# schemat.net
KiCad netlist of a schematic drawn in EAGLE
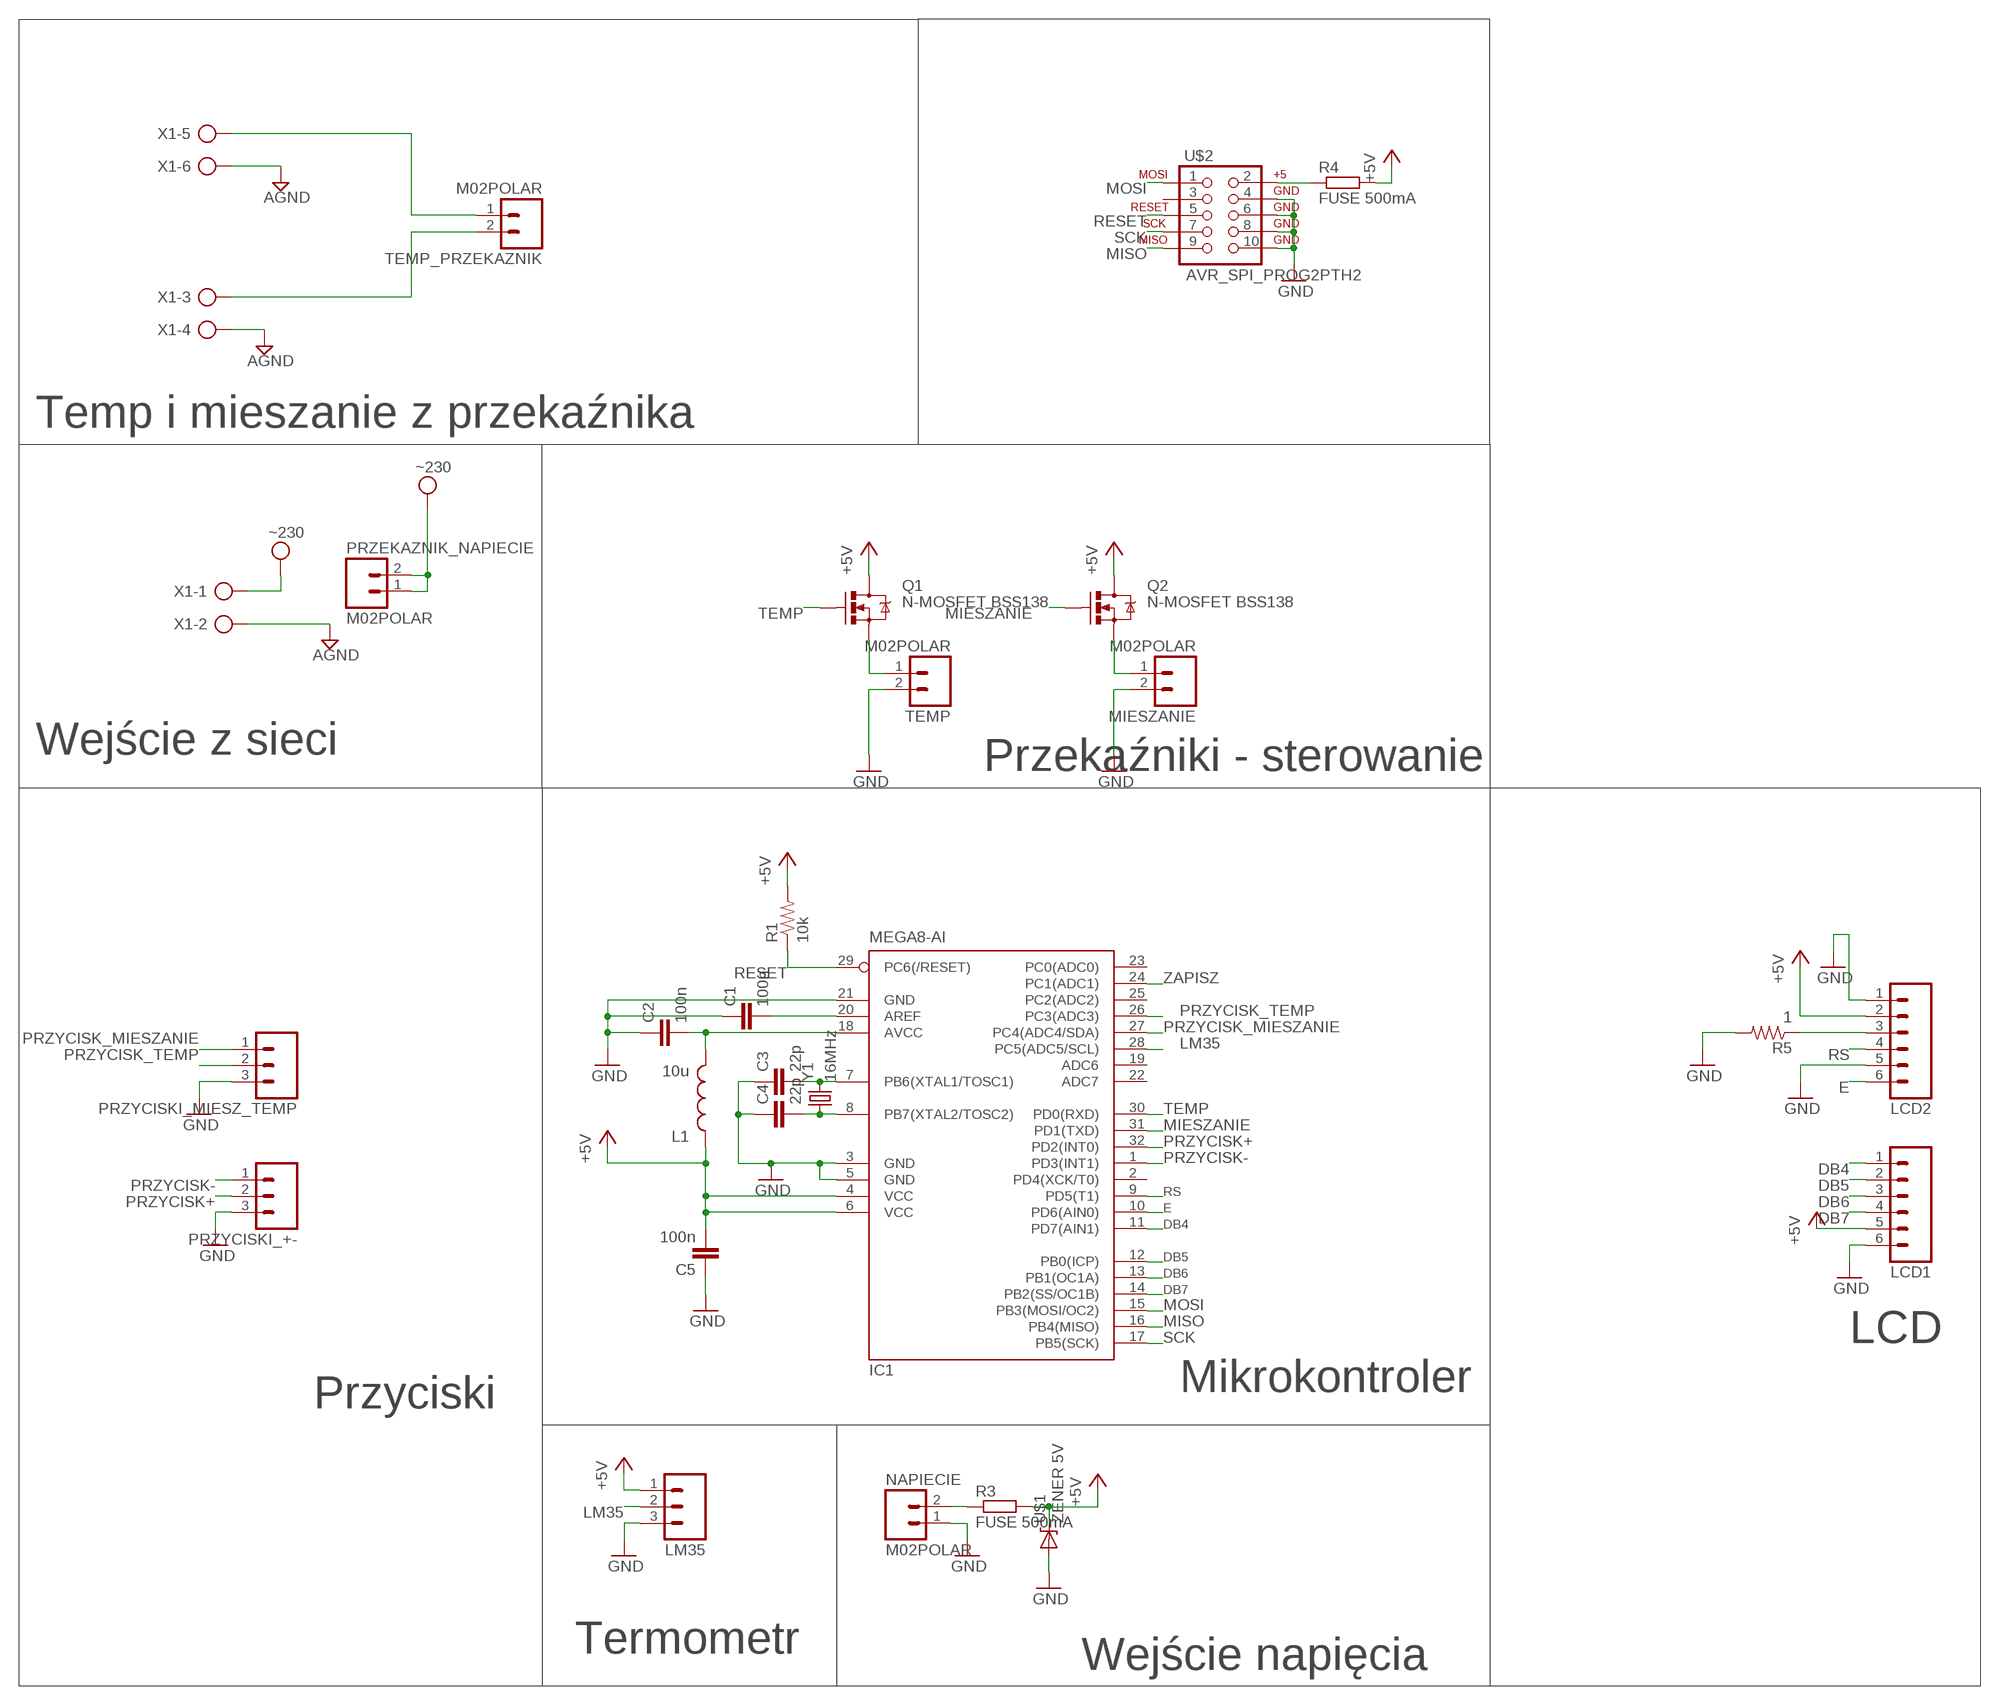
[diagram p0: schematic, sheet 1]

(export (version "E")
  (design (tool "Eeschema 10.0.6"))
  (components
    (comp (ref "C1")
      (value "100n")
      (footprint "eagle-import:0805")
      (libsource (lib "eagle-import") (part "CAP0805"))
    )
    (comp (ref "C2")
      (value "100n")
      (footprint "eagle-import:0805")
      (libsource (lib "eagle-import") (part "CAP0805"))
    )
    (comp (ref "C3")
      (value "22p")
      (footprint "eagle-import:0805")
      (libsource (lib "eagle-import") (part "CAP0805"))
    )
    (comp (ref "C4")
      (value "22p")
      (footprint "eagle-import:0805")
      (libsource (lib "eagle-import") (part "CAP0805"))
    )
    (comp (ref "C5")
      (value "100n")
      (footprint "eagle-import:0805")
      (libsource (lib "eagle-import") (part "CAP0805"))
    )
    (comp (ref "IC1")
      (value "MEGA8-AI")
      (footprint "eagle-import:TQFP32-08")
      (fields (field (name "MPN") "ATMEGA8-16AU"))
      (libsource (lib "eagle-import") (part "MEGA8-AI"))
    )
    (comp (ref "L1")
      (value "10u")
      (footprint "eagle-import:0805")
      (libsource (lib "eagle-import") (part "INDUCTOR0805"))
    )
    (comp (ref "LCD1")
      (value "M06POLAR")
      (footprint "eagle-import:MOLEX-1X6")
      (libsource (lib "eagle-import") (part "M06POLAR"))
    )
    (comp (ref "LCD2")
      (value "M06POLAR")
      (footprint "eagle-import:MOLEX-1X6")
      (libsource (lib "eagle-import") (part "M06POLAR"))
    )
    (comp (ref "LM35")
      (value "M03POLAR")
      (footprint "eagle-import:MOLEX-1X3")
      (libsource (lib "eagle-import") (part "M03POLAR"))
    )
    (comp (ref "MIESZANIE")
      (value "M02POLAR")
      (footprint "eagle-import:MOLEX-1X2")
      (libsource (lib "eagle-import") (part "M02POLAR"))
    )
    (comp (ref "NAPIECIE")
      (value "M02POLAR")
      (footprint "eagle-import:MOLEX-1X2")
      (libsource (lib "eagle-import") (part "M02POLAR"))
    )
    (comp (ref "PRZEKAZNIK_NAPIECIE")
      (value "M02POLAR")
      (footprint "eagle-import:MOLEX-1X2")
      (libsource (lib "eagle-import") (part "M02POLAR"))
    )
    (comp (ref "PRZYCISKI_+-")
      (value "M03POLAR")
      (footprint "eagle-import:MOLEX-1X3")
      (libsource (lib "eagle-import") (part "M03POLAR"))
    )
    (comp (ref "PRZYCISKI_MIESZ_TEMP")
      (value "M03POLAR")
      (footprint "eagle-import:MOLEX-1X3")
      (libsource (lib "eagle-import") (part "M03POLAR"))
    )
    (comp (ref "Q1")
      (value "N-MOSFET BSS138")
      (footprint "eagle-import:SOT23")
      (libsource (lib "eagle-import") (part "MOSFET-NCHANNELBSS123LT1G"))
    )
    (comp (ref "Q2")
      (value "N-MOSFET BSS138")
      (footprint "eagle-import:SOT23")
      (libsource (lib "eagle-import") (part "MOSFET-NCHANNELBSS123LT1G"))
    )
    (comp (ref "R1")
      (value "10k")
      (footprint "eagle-import:0805")
      (libsource (lib "eagle-import") (part "RESISTOR0805-RES"))
    )
    (comp (ref "R3")
      (value "FUSE 500mA")
      (footprint "eagle-import:M0805")
      (libsource (lib "eagle-import") (part "R-EU_M0805"))
    )
    (comp (ref "R4")
      (value "FUSE 500mA")
      (footprint "eagle-import:M0805")
      (libsource (lib "eagle-import") (part "R-EU_M0805"))
    )
    (comp (ref "R5")
      (value "1")
      (footprint "eagle-import:0805")
      (libsource (lib "eagle-import") (part "RESISTOR0805-RES"))
    )
    (comp (ref "TEMP")
      (value "M02POLAR")
      (footprint "eagle-import:MOLEX-1X2")
      (libsource (lib "eagle-import") (part "M02POLAR"))
    )
    (comp (ref "TEMP_PRZEKAZNIK")
      (value "M02POLAR")
      (footprint "eagle-import:MOLEX-1X2")
      (libsource (lib "eagle-import") (part "M02POLAR"))
    )
    (comp (ref "U$1")
      (value "ZENER 5V")
      (footprint "eagle-import:SMB-DIODE")
      (libsource (lib "eagle-import") (part "DIODE-ZENERSMB"))
    )
    (comp (ref "U$2")
      (value "AVR_SPI_PROG2PTH2")
      (footprint "eagle-import:2X5-SHROUDED")
      (libsource (lib "eagle-import") (part "AVR_SPI_PROG2PTH2"))
    )
    (comp (ref "X1")
      (value "AK300/6")
      (footprint "eagle-import:AK300_6")
      (libsource (lib "eagle-import") (part "AK300/6"))
    )
    (comp (ref "Y1")
      (value "16MHz")
      (footprint "eagle-import:HC49US")
      (libsource (lib "eagle-import") (part "CRYSTALHC49US"))
    )
  )
  (nets
    (net (code "1") (name "+5V") (class "Default")
      (node (ref "C5") (pin "2") (pinfunction "2_2") (pintype "passive"))
      (node (ref "IC1") (pin "4") (pinfunction "VCC_4") (pintype "power_in"))
      (node (ref "IC1") (pin "6") (pinfunction "VCC_6") (pintype "power_in"))
      (node (ref "L1") (pin "1") (pinfunction "1_1") (pintype "passive"))
      (node (ref "LCD1") (pin "5") (pinfunction "5_5") (pintype "passive"))
      (node (ref "LCD2") (pin "2") (pinfunction "2_2") (pintype "passive"))
      (node (ref "LM35") (pin "1") (pinfunction "1_1") (pintype "passive"))
      (node (ref "Q1") (pin "3") (pinfunction "D_3") (pintype "passive"))
      (node (ref "Q2") (pin "3") (pinfunction "D_3") (pintype "passive"))
      (node (ref "R1") (pin "2") (pinfunction "2_2") (pintype "passive"))
      (node (ref "R3") (pin "2") (pinfunction "2_2") (pintype "passive"))
      (node (ref "R4") (pin "2") (pinfunction "2_2") (pintype "passive"))
      (node (ref "U$1") (pin "C") (pinfunction "C_C") (pintype "passive"))
    )
    (net (code "2") (name "/DB4") (class "Default")
      (node (ref "IC1") (pin "11") (pinfunction "PD7(AIN1)_11") (pintype "bidirectional"))
      (node (ref "LCD1") (pin "1") (pinfunction "1_1") (pintype "passive"))
    )
    (net (code "3") (name "/DB5") (class "Default")
      (node (ref "IC1") (pin "12") (pinfunction "PB0(ICP)_12") (pintype "bidirectional"))
      (node (ref "LCD1") (pin "2") (pinfunction "2_2") (pintype "passive"))
    )
    (net (code "4") (name "/DB6") (class "Default")
      (node (ref "IC1") (pin "13") (pinfunction "PB1(OC1A)_13") (pintype "bidirectional"))
      (node (ref "LCD1") (pin "3") (pinfunction "3_3") (pintype "passive"))
    )
    (net (code "5") (name "/DB7") (class "Default")
      (node (ref "IC1") (pin "14") (pinfunction "PB2(SS/OC1B)_14") (pintype "bidirectional"))
      (node (ref "LCD1") (pin "4") (pinfunction "4_4") (pintype "passive"))
    )
    (net (code "6") (name "/E") (class "Default")
      (node (ref "IC1") (pin "10") (pinfunction "PD6(AIN0)_10") (pintype "bidirectional"))
      (node (ref "LCD2") (pin "6") (pinfunction "6_6") (pintype "passive"))
    )
    (net (code "7") (name "/LM35") (class "Default")
      (node (ref "IC1") (pin "28") (pinfunction "PC5(ADC5/SCL)_28") (pintype "bidirectional"))
      (node (ref "LM35") (pin "2") (pinfunction "2_2") (pintype "passive"))
    )
    (net (code "8") (name "/MIESZANIE") (class "Default")
      (node (ref "IC1") (pin "31") (pinfunction "PD1(TXD)_31") (pintype "bidirectional"))
      (node (ref "Q2") (pin "1") (pinfunction "G_1") (pintype "passive"))
    )
    (net (code "9") (name "/MISO") (class "Default")
      (node (ref "IC1") (pin "16") (pinfunction "PB4(MISO)_16") (pintype "bidirectional"))
      (node (ref "U$2") (pin "9") (pinfunction "9_9") (pintype "passive"))
    )
    (net (code "10") (name "/MOSI") (class "Default")
      (node (ref "IC1") (pin "15") (pinfunction "PB3(MOSI/OC2)_15") (pintype "bidirectional"))
      (node (ref "U$2") (pin "1") (pinfunction "1_1") (pintype "passive"))
    )
    (net (code "11") (name "/PRZYCISK+") (class "Default")
      (node (ref "IC1") (pin "32") (pinfunction "PD2(INT0)_32") (pintype "bidirectional"))
      (node (ref "PRZYCISKI_+-") (pin "2") (pinfunction "2_2") (pintype "passive"))
    )
    (net (code "12") (name "/PRZYCISK-") (class "Default")
      (node (ref "IC1") (pin "1") (pinfunction "PD3(INT1)_1") (pintype "bidirectional"))
      (node (ref "PRZYCISKI_+-") (pin "1") (pinfunction "1_1") (pintype "passive"))
    )
    (net (code "13") (name "/PRZYCISK_MIESZANIE") (class "Default")
      (node (ref "IC1") (pin "27") (pinfunction "PC4(ADC4/SDA)_27") (pintype "bidirectional"))
      (node (ref "PRZYCISKI_MIESZ_TEMP") (pin "1") (pinfunction "1_1") (pintype "passive"))
    )
    (net (code "14") (name "/PRZYCISK_TEMP") (class "Default")
      (node (ref "IC1") (pin "26") (pinfunction "PC3(ADC3)_26") (pintype "bidirectional"))
      (node (ref "PRZYCISKI_MIESZ_TEMP") (pin "2") (pinfunction "2_2") (pintype "passive"))
    )
    (net (code "15") (name "/RESET") (class "Default")
      (node (ref "IC1") (pin "29") (pinfunction "PC6(/RESET)_29") (pintype "bidirectional"))
      (node (ref "R1") (pin "1") (pinfunction "1_1") (pintype "passive"))
      (node (ref "U$2") (pin "5") (pinfunction "5_5") (pintype "passive"))
    )
    (net (code "16") (name "/RS") (class "Default")
      (node (ref "IC1") (pin "9") (pinfunction "PD5(T1)_9") (pintype "bidirectional"))
      (node (ref "LCD2") (pin "4") (pinfunction "4_4") (pintype "passive"))
    )
    (net (code "17") (name "/SCK") (class "Default")
      (node (ref "IC1") (pin "17") (pinfunction "PB5(SCK)_17") (pintype "bidirectional"))
      (node (ref "U$2") (pin "7") (pinfunction "7_7") (pintype "passive"))
    )
    (net (code "18") (name "/TEMP") (class "Default")
      (node (ref "IC1") (pin "30") (pinfunction "PD0(RXD)_30") (pintype "bidirectional"))
      (node (ref "Q1") (pin "1") (pinfunction "G_1") (pintype "passive"))
    )
    (net (code "19") (name "/ZAPISZ") (class "Default")
      (node (ref "IC1") (pin "24") (pinfunction "PC1(ADC1)_24") (pintype "bidirectional"))
    )
    (net (code "20") (name "AGND") (class "Default")
      (node (ref "X1") (pin "2") (pinfunction "KL_2") (pintype "passive"))
      (node (ref "X1") (pin "4") (pinfunction "KL_4") (pintype "passive"))
      (node (ref "X1") (pin "6") (pinfunction "KL_6") (pintype "passive"))
    )
    (net (code "21") (name "GND") (class "Default")
      (node (ref "C1") (pin "1") (pinfunction "1_1") (pintype "passive"))
      (node (ref "C2") (pin "1") (pinfunction "1_1") (pintype "passive"))
      (node (ref "C3") (pin "1") (pinfunction "1_1") (pintype "passive"))
      (node (ref "C4") (pin "1") (pinfunction "1_1") (pintype "passive"))
      (node (ref "C5") (pin "1") (pinfunction "1_1") (pintype "passive"))
      (node (ref "IC1") (pin "21") (pinfunction "GND_21") (pintype "power_in"))
      (node (ref "IC1") (pin "3") (pinfunction "GND_3") (pintype "power_in"))
      (node (ref "IC1") (pin "5") (pinfunction "GND_5") (pintype "power_in"))
      (node (ref "LCD1") (pin "6") (pinfunction "6_6") (pintype "passive"))
      (node (ref "LCD2") (pin "1") (pinfunction "1_1") (pintype "passive"))
      (node (ref "LCD2") (pin "5") (pinfunction "5_5") (pintype "passive"))
      (node (ref "LM35") (pin "3") (pinfunction "3_3") (pintype "passive"))
      (node (ref "MIESZANIE") (pin "2") (pinfunction "2_2") (pintype "passive"))
      (node (ref "NAPIECIE") (pin "1") (pinfunction "1_1") (pintype "passive"))
      (node (ref "PRZYCISKI_+-") (pin "3") (pinfunction "3_3") (pintype "passive"))
      (node (ref "PRZYCISKI_MIESZ_TEMP") (pin "3") (pinfunction "3_3") (pintype "passive"))
      (node (ref "R5") (pin "2") (pinfunction "2_2") (pintype "passive"))
      (node (ref "TEMP") (pin "2") (pinfunction "2_2") (pintype "passive"))
      (node (ref "U$1") (pin "A") (pinfunction "A_A") (pintype "passive"))
      (node (ref "U$2") (pin "10") (pinfunction "10_10") (pintype "passive"))
      (node (ref "U$2") (pin "4") (pinfunction "4_4") (pintype "passive"))
      (node (ref "U$2") (pin "6") (pinfunction "6_6") (pintype "passive"))
      (node (ref "U$2") (pin "8") (pinfunction "8_8") (pintype "passive"))
    )
    (net (code "22") (name "Net-(IC1-AREF)") (class "Default")
      (node (ref "C1") (pin "2") (pinfunction "2_2") (pintype "passive"))
      (node (ref "IC1") (pin "20") (pinfunction "AREF_20") (pintype "passive"))
    )
    (net (code "23") (name "Net-(IC1-AVCC)") (class "Default")
      (node (ref "C2") (pin "2") (pinfunction "2_2") (pintype "passive"))
      (node (ref "IC1") (pin "18") (pinfunction "AVCC_18") (pintype "power_in"))
      (node (ref "L1") (pin "2") (pinfunction "2_2") (pintype "passive"))
    )
    (net (code "24") (name "Net-(IC1-PB6(XTAL1{slash}TOSC1))") (class "Default")
      (node (ref "C3") (pin "2") (pinfunction "2_2") (pintype "passive"))
      (node (ref "IC1") (pin "7") (pinfunction "PB6(XTAL1/TOSC1)_7") (pintype "bidirectional"))
      (node (ref "Y1") (pin "2") (pinfunction "2_2") (pintype "passive"))
    )
    (net (code "25") (name "Net-(IC1-PB7(XTAL2{slash}TOSC2))") (class "Default")
      (node (ref "C4") (pin "2") (pinfunction "2_2") (pintype "passive"))
      (node (ref "IC1") (pin "8") (pinfunction "PB7(XTAL2/TOSC2)_8") (pintype "bidirectional"))
      (node (ref "Y1") (pin "1") (pinfunction "1_1") (pintype "passive"))
    )
    (net (code "26") (name "Net-(LCD2-Pad3)") (class "Default")
      (node (ref "LCD2") (pin "3") (pinfunction "3_3") (pintype "passive"))
      (node (ref "R5") (pin "1") (pinfunction "1_1") (pintype "passive"))
    )
    (net (code "27") (name "Net-(NAPIECIE-Pad2)") (class "Default")
      (node (ref "NAPIECIE") (pin "2") (pinfunction "2_2") (pintype "passive"))
      (node (ref "R3") (pin "1") (pinfunction "1_1") (pintype "passive"))
    )
    (net (code "28") (name "Net-(Q1-S)") (class "Default")
      (node (ref "Q1") (pin "2") (pinfunction "S_2") (pintype "passive"))
      (node (ref "TEMP") (pin "1") (pinfunction "1_1") (pintype "passive"))
    )
    (net (code "29") (name "Net-(Q2-S)") (class "Default")
      (node (ref "MIESZANIE") (pin "1") (pinfunction "1_1") (pintype "passive"))
      (node (ref "Q2") (pin "2") (pinfunction "S_2") (pintype "passive"))
    )
    (net (code "30") (name "Net-(R4-Pad1)") (class "Default")
      (node (ref "R4") (pin "1") (pinfunction "1_1") (pintype "passive"))
      (node (ref "U$2") (pin "2") (pinfunction "2_2") (pintype "passive"))
    )
    (net (code "31") (name "Net-(X1C-KL)") (class "Default")
      (node (ref "TEMP_PRZEKAZNIK") (pin "2") (pinfunction "2_2") (pintype "passive"))
      (node (ref "X1") (pin "3") (pinfunction "KL_3") (pintype "passive"))
    )
    (net (code "32") (name "Net-(X1E-KL)") (class "Default")
      (node (ref "TEMP_PRZEKAZNIK") (pin "1") (pinfunction "1_1") (pintype "passive"))
      (node (ref "X1") (pin "5") (pinfunction "KL_5") (pintype "passive"))
    )
    (net (code "33") (name "unconnected-(IC1-ADC6-Pad19)") (class "Default")
      (node (ref "IC1") (pin "19") (pinfunction "ADC6_19") (pintype "bidirectional"))
    )
    (net (code "34") (name "unconnected-(IC1-ADC7-Pad22)") (class "Default")
      (node (ref "IC1") (pin "22") (pinfunction "ADC7_22") (pintype "bidirectional"))
    )
    (net (code "35") (name "unconnected-(IC1-PC0(ADC0)-Pad23)") (class "Default")
      (node (ref "IC1") (pin "23") (pinfunction "PC0(ADC0)_23") (pintype "bidirectional"))
    )
    (net (code "36") (name "unconnected-(IC1-PC2(ADC2)-Pad25)") (class "Default")
      (node (ref "IC1") (pin "25") (pinfunction "PC2(ADC2)_25") (pintype "bidirectional"))
    )
    (net (code "37") (name "unconnected-(IC1-PD4(XCK{slash}T0)-Pad2)") (class "Default")
      (node (ref "IC1") (pin "2") (pinfunction "PD4(XCK/T0)_2") (pintype "bidirectional"))
    )
    (net (code "38") (name "unconnected-(U$2-Pad3)") (class "Default")
      (node (ref "U$2") (pin "3") (pinfunction "3_3") (pintype "passive"))
    )
    (net (code "39") (name "~230") (class "Default")
      (node (ref "PRZEKAZNIK_NAPIECIE") (pin "1") (pinfunction "1_1") (pintype "passive"))
      (node (ref "PRZEKAZNIK_NAPIECIE") (pin "2") (pinfunction "2_2") (pintype "passive"))
      (node (ref "X1") (pin "1") (pinfunction "KL_1") (pintype "passive"))
    )
  )
)
